# Sheet_1_2022-08-21.net
KiCad netlist of a schematic drawn in Altium Designer
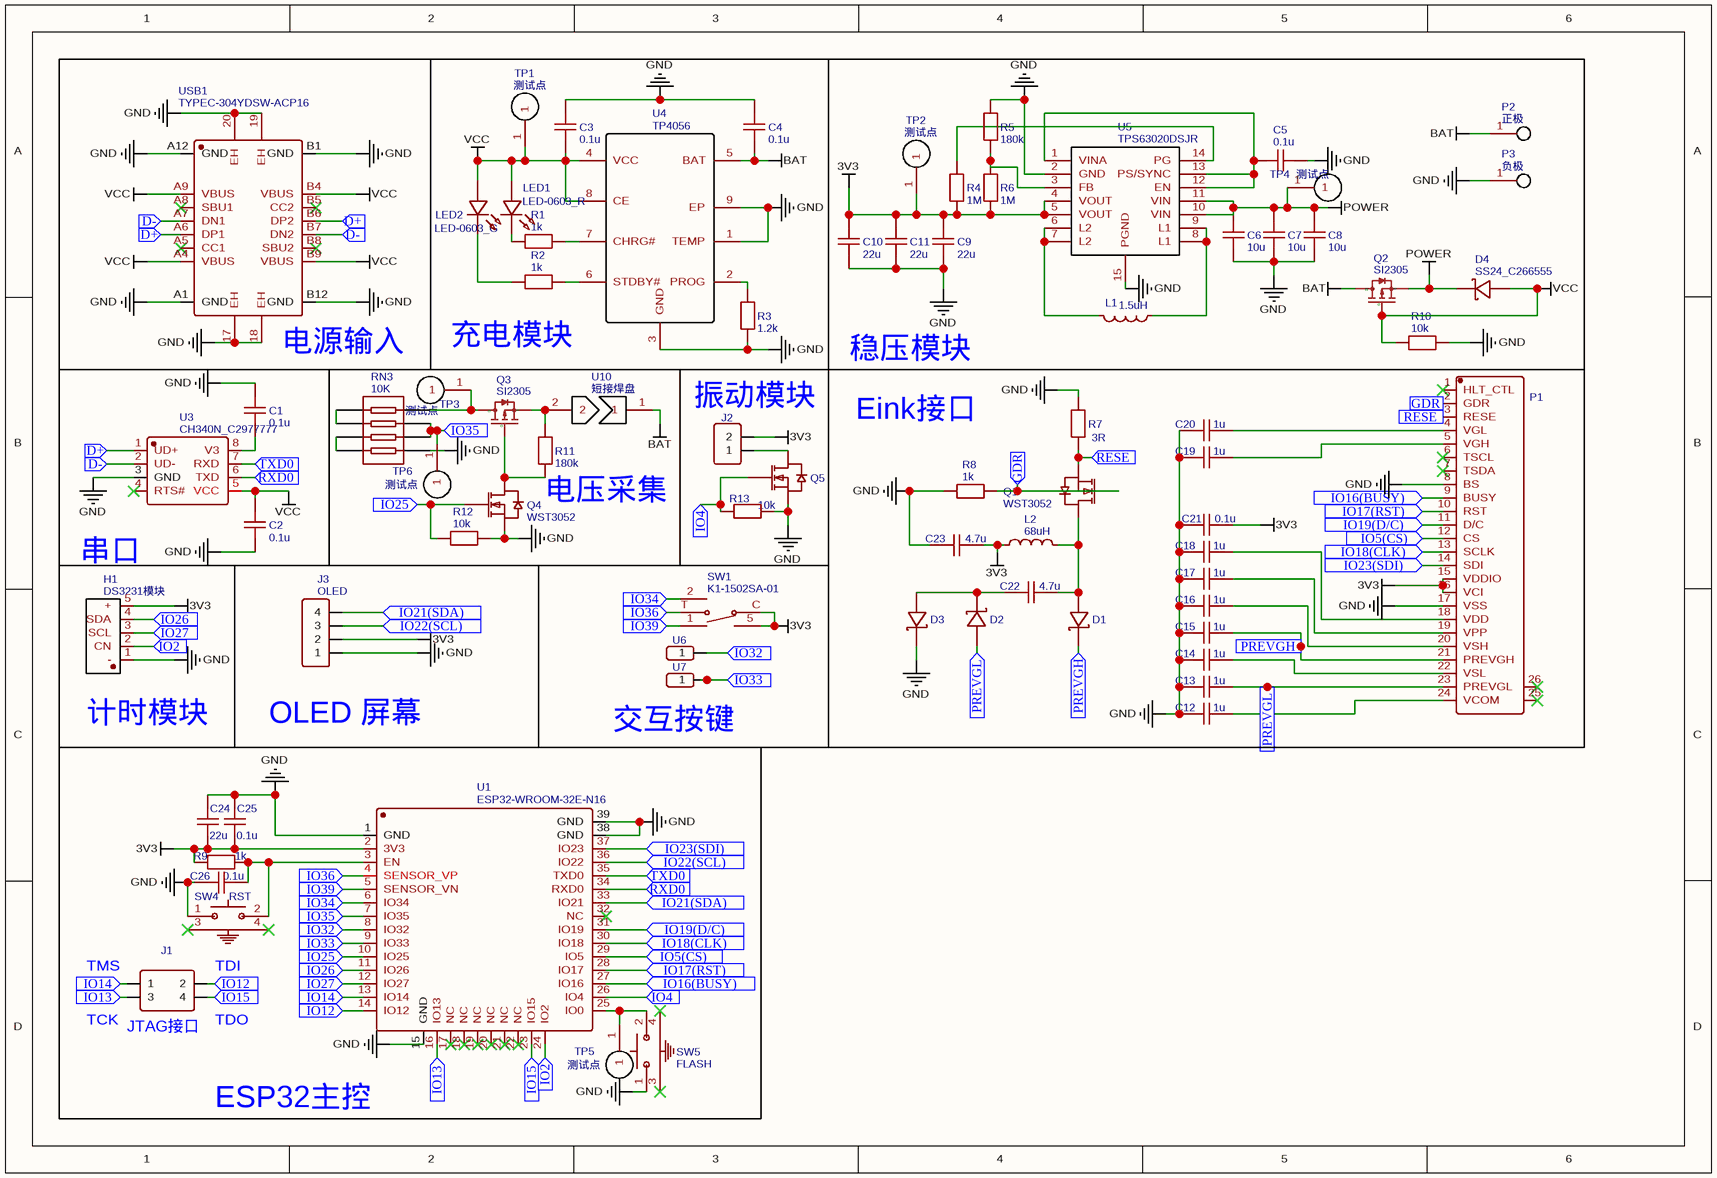
[diagram p0: Sheet_1_2022-08-21.schdoc]

(export (version "E")
  (design (tool "Eeschema 10.0.6"))
  (components
    (comp (ref "C1")
      (value "0.1u")
      (fields (field (name "CONTRIBUTOR") "LCEDA_Lib"))
      (libsource (lib "altium-import") (part "root_1_0.1u_"))
    )
    (comp (ref "C2")
      (value "0.1u")
      (fields (field (name "CONTRIBUTOR") "LCEDA_Lib"))
      (libsource (lib "altium-import") (part "root_1_0.1u_"))
    )
    (comp (ref "C3")
      (value "0.1u")
      (fields (field (name "CONTRIBUTOR") "LCEDA_Lib"))
      (libsource (lib "altium-import") (part "root_1_0.1u_"))
    )
    (comp (ref "C4")
      (value "0.1u")
      (fields (field (name "CONTRIBUTOR") "LCEDA_Lib"))
      (libsource (lib "altium-import") (part "root_1_0.1u_"))
    )
    (comp (ref "C5")
      (value "0.1u")
      (fields (field (name "CONTRIBUTOR") "LCEDA_Lib"))
      (libsource (lib "altium-import") (part "root_0_0.1u_"))
    )
    (comp (ref "C6")
      (value "10u")
      (fields (field (name "CONTRIBUTOR") "LCEDA_Lib"))
      (libsource (lib "altium-import") (part "root_1_10u_"))
    )
    (comp (ref "C7")
      (value "10u")
      (fields (field (name "CONTRIBUTOR") "LCEDA_Lib"))
      (libsource (lib "altium-import") (part "root_1_10u_"))
    )
    (comp (ref "C8")
      (value "10u")
      (fields (field (name "CONTRIBUTOR") "LCEDA_Lib"))
      (libsource (lib "altium-import") (part "root_1_10u_"))
    )
    (comp (ref "C9")
      (value "22u")
      (fields (field (name "CONTRIBUTOR") "LCEDA_Lib"))
      (libsource (lib "altium-import") (part "root_1_22u_"))
    )
    (comp (ref "C10")
      (value "22u")
      (fields (field (name "CONTRIBUTOR") "LCEDA_Lib"))
      (libsource (lib "altium-import") (part "root_1_22u_"))
    )
    (comp (ref "C11")
      (value "22u")
      (fields (field (name "CONTRIBUTOR") "LCEDA_Lib"))
      (libsource (lib "altium-import") (part "root_1_22u_"))
    )
    (comp (ref "C12")
      (value "1u")
      (fields (field (name "CONTRIBUTOR") "LCEDA_Lib"))
      (libsource (lib "altium-import") (part "root_0_1u_"))
    )
    (comp (ref "C13")
      (value "1u")
      (fields (field (name "CONTRIBUTOR") "LCEDA_Lib"))
      (libsource (lib "altium-import") (part "root_0_1u_"))
    )
    (comp (ref "C14")
      (value "1u")
      (fields (field (name "CONTRIBUTOR") "LCEDA_Lib"))
      (libsource (lib "altium-import") (part "root_2_1u_"))
    )
    (comp (ref "C15")
      (value "1u")
      (fields (field (name "CONTRIBUTOR") "LCEDA_Lib"))
      (libsource (lib "altium-import") (part "root_0_1u_"))
    )
    (comp (ref "C16")
      (value "1u")
      (fields (field (name "CONTRIBUTOR") "LCEDA_Lib"))
      (libsource (lib "altium-import") (part "root_0_1u_"))
    )
    (comp (ref "C17")
      (value "1u")
      (fields (field (name "CONTRIBUTOR") "LCEDA_Lib"))
      (libsource (lib "altium-import") (part "root_0_1u_"))
    )
    (comp (ref "C18")
      (value "1u")
      (fields (field (name "CONTRIBUTOR") "LCEDA_Lib"))
      (libsource (lib "altium-import") (part "root_0_1u_"))
    )
    (comp (ref "C19")
      (value "1u")
      (fields (field (name "CONTRIBUTOR") "LCEDA_Lib"))
      (libsource (lib "altium-import") (part "root_0_1u_"))
    )
    (comp (ref "C20")
      (value "1u")
      (fields (field (name "CONTRIBUTOR") "LCEDA_Lib"))
      (libsource (lib "altium-import") (part "root_0_1u_"))
    )
    (comp (ref "C21")
      (value "0.1u")
      (fields (field (name "CONTRIBUTOR") "LCEDA_Lib"))
      (libsource (lib "altium-import") (part "root_0_0.1u_"))
    )
    (comp (ref "C22")
      (value "4.7u")
      (fields (field (name "CONTRIBUTOR") "LCEDA_Lib"))
      (libsource (lib "altium-import") (part "root_0_4.7u_"))
    )
    (comp (ref "C23")
      (value "4.7u")
      (fields (field (name "CONTRIBUTOR") "LCEDA_Lib"))
      (libsource (lib "altium-import") (part "root_0_4.7u_"))
    )
    (comp (ref "C24")
      (value "22u")
      (fields (field (name "CONTRIBUTOR") "LCEDA_Lib"))
      (libsource (lib "altium-import") (part "root_1_22u_"))
    )
    (comp (ref "C25")
      (value "0.1u")
      (fields (field (name "CONTRIBUTOR") "LCEDA_Lib"))
      (libsource (lib "altium-import") (part "root_1_0.1u_"))
    )
    (comp (ref "C26")
      (value "0.1u")
      (fields (field (name "CONTRIBUTOR") "LCEDA_Lib"))
      (libsource (lib "altium-import") (part "root_2_0.1u_"))
    )
    (comp (ref "D1")
      (value "MBR0530_C232832")
      (fields
        (field (name "BOM_SUPPLIER PART") "C232832")
        (field (name "BOM_MANUFACTURER PART") "MBR0530")
        (field (name "CONTRIBUTOR") "LCSC")
      )
      (libsource (lib "altium-import") (part "root_1_MBR0530_C232832_"))
    )
    (comp (ref "D2")
      (value "MBR0530_C232832")
      (fields
        (field (name "BOM_SUPPLIER PART") "C232832")
        (field (name "BOM_MANUFACTURER PART") "MBR0530")
        (field (name "CONTRIBUTOR") "LCSC")
      )
      (libsource (lib "altium-import") (part "root_3_MBR0530_C232832_"))
    )
    (comp (ref "D3")
      (value "MBR0530_C232832")
      (fields
        (field (name "BOM_SUPPLIER PART") "C232832")
        (field (name "BOM_MANUFACTURER PART") "MBR0530")
        (field (name "CONTRIBUTOR") "LCSC")
      )
      (libsource (lib "altium-import") (part "root_1_MBR0530_C232832_"))
    )
    (comp (ref "D4")
      (value "SS24_C266555")
      (fields
        (field (name "BOM_SUPPLIER PART") "C266555")
        (field (name "BOM_MANUFACTURER PART") "SS24")
        (field (name "CONTRIBUTOR") "LCSC")
      )
      (libsource (lib "altium-import") (part "root_0_SS24_C266555_"))
    )
    (comp (ref "H1")
      (value "DS3231模块")
      (fields
        (field (name "BOM_SUPPLIER PART") "C492404")
        (field (name "BOM_MANUFACTURER PART") "PZ254V-11-05P")
        (field (name "CONTRIBUTOR") "LCSC")
      )
      (libsource (lib "altium-import") (part "root_2_DS3231模块_"))
    )
    (comp (ref "J1")
      (value "HDR-M-2.54_2x2")
      (fields (field (name "BOM_SUPPLIER PART") "C66690") (field (name "CONTRIBUTOR") "LCEDA_Lib"))
      (libsource (lib "altium-import") (part "root_0_HDR-M-2.54_2x2_"))
    )
    (comp (ref "J2")
      (value "HDR-M-2.54_1x2")
      (fields (field (name "BOM_SUPPLIER PART") "C124375") (field (name "CONTRIBUTOR") "LCEDA_Lib"))
      (libsource (lib "altium-import") (part "root_2_HDR-M-2.54_1x2_"))
    )
    (comp (ref "J3")
      (value "OLED")
      (fields (field (name "BOM_SUPPLIER PART") "C124378") (field (name "CONTRIBUTOR") "LCEDA_Lib"))
      (libsource (lib "altium-import") (part "root_2_OLED_"))
    )
    (comp (ref "L1")
      (value "1.5uH")
      (fields
        (field (name "BOM_SUPPLIER PART") "C340206")
        (field (name "BOM_MANUFACTURER PART") "ASWPA4035S1R5MT")
        (field (name "CONTRIBUTOR") "LCSC")
      )
      (libsource (lib "altium-import") (part "root_2_1.5uH_"))
    )
    (comp (ref "L2")
      (value "68uH")
      (fields
        (field (name "BOM_SUPPLIER PART") "C340229")
        (field (name "BOM_MANUFACTURER PART") "ASWPA6055S680MT")
        (field (name "CONTRIBUTOR") "LCSC")
      )
      (libsource (lib "altium-import") (part "root_0_68uH_"))
    )
    (comp (ref "LED1")
      (value "LED-0603_R")
      (fields
        (field (name "BOM_MANUFACTURER PART") "19-217/R6C-AL1M2VY/3T")
        (field (name "BOM_SUPPLIER PART") "C72044")
        (field (name "CONTRIBUTOR") "LCEDA_01")
      )
      (libsource (lib "altium-import") (part "root_3_LED-0603_R_"))
    )
    (comp (ref "LED2")
      (value "LED-0603_G")
      (fields
        (field (name "BOM_MANUFACTURER PART") "19-217/GHC-YR1S2/3T")
        (field (name "BOM_SUPPLIER PART") "C72043")
        (field (name "CONTRIBUTOR") "LCEDA_Lib")
      )
      (libsource (lib "altium-import") (part "root_3_LED-0603_G_"))
    )
    (comp (ref "P1")
      (value "微雪电子 24pin 电子墨水屏幕底座  /FPC 0.5MM 24P")
      (fields
        (field (name "BOM_MANUFACTURER PART") "FPC 0.5MM 24P Pull type H2.0mm Under the next")
        (field (name "BOM_SUPPLIER PART") "C11057")
        (field (name "CONTRIBUTOR") "jszszzy")
      )
      (libsource (lib "altium-import") (part "root_0_微雪电子 24pin 电子墨水屏幕底座  /FPC 0.5MM 24P_"))
    )
    (comp (ref "P2")
      (value "正极")
      (fields (field (name "CONTRIBUTOR") "Newguy"))
      (libsource (lib "altium-import") (part "root_2_正极_"))
    )
    (comp (ref "P3")
      (value "负极")
      (fields (field (name "CONTRIBUTOR") "Newguy"))
      (libsource (lib "altium-import") (part "root_2_负极_"))
    )
    (comp (ref "Q1")
      (value "WST3052")
      (fields (field (name "BOM_SUPPLIER PART") "C719079") (field (name "CONTRIBUTOR") "LCSC"))
      (libsource (lib "altium-import") (part "root_2_WST3052_"))
    )
    (comp (ref "Q2")
      (value "SI2305")
      (fields (field (name "BOM_SUPPLIER PART") "C181088") (field (name "CONTRIBUTOR") "LCSC"))
      (libsource (lib "altium-import") (part "root_1_SI2305_"))
    )
    (comp (ref "Q3")
      (value "SI2305")
      (fields (field (name "BOM_SUPPLIER PART") "C181088") (field (name "CONTRIBUTOR") "LCSC"))
      (libsource (lib "altium-import") (part "root_1_SI2305_"))
    )
    (comp (ref "Q4")
      (value "WST3052")
      (fields (field (name "BOM_SUPPLIER PART") "C719079") (field (name "CONTRIBUTOR") "LCSC"))
      (libsource (lib "altium-import") (part "root_0_WST3052_"))
    )
    (comp (ref "Q5")
      (value "WST3052")
      (fields (field (name "BOM_SUPPLIER PART") "C719079") (field (name "CONTRIBUTOR") "LCSC"))
      (libsource (lib "altium-import") (part "root_0_WST3052_"))
    )
    (comp (ref "R1")
      (value "1k")
      (fields (field (name "CONTRIBUTOR") "LCEDA_Lib"))
      (libsource (lib "altium-import") (part "root_0_1k_"))
    )
    (comp (ref "R2")
      (value "1k")
      (fields (field (name "CONTRIBUTOR") "LCEDA_Lib"))
      (libsource (lib "altium-import") (part "root_0_1k_"))
    )
    (comp (ref "R3")
      (value "1.2k")
      (fields (field (name "CONTRIBUTOR") "LCEDA_Lib"))
      (libsource (lib "altium-import") (part "root_1_1.2k_"))
    )
    (comp (ref "R4")
      (value "1M")
      (fields (field (name "CONTRIBUTOR") "LCEDA_Lib"))
      (libsource (lib "altium-import") (part "root_1_1M_"))
    )
    (comp (ref "R5")
      (value "180k")
      (fields (field (name "CONTRIBUTOR") "LCEDA_Lib"))
      (libsource (lib "altium-import") (part "root_1_180k_"))
    )
    (comp (ref "R6")
      (value "1M")
      (fields (field (name "CONTRIBUTOR") "LCEDA_Lib"))
      (libsource (lib "altium-import") (part "root_1_1M_"))
    )
    (comp (ref "R7")
      (value "3R")
      (fields (field (name "CONTRIBUTOR") "LCEDA_Lib"))
      (libsource (lib "altium-import") (part "root_1_3R_"))
    )
    (comp (ref "R8")
      (value "1k")
      (fields (field (name "CONTRIBUTOR") "LCEDA_Lib"))
      (libsource (lib "altium-import") (part "root_2_1k_"))
    )
    (comp (ref "R9")
      (value "1k")
      (fields (field (name "CONTRIBUTOR") "LCEDA_Lib"))
      (libsource (lib "altium-import") (part "root_0_1k_"))
    )
    (comp (ref "R10")
      (value "10k")
      (fields (field (name "CONTRIBUTOR") "LCEDA_Lib"))
      (libsource (lib "altium-import") (part "root_2_10k_"))
    )
    (comp (ref "R11")
      (value "180k")
      (fields (field (name "CONTRIBUTOR") "LCEDA_Lib"))
      (libsource (lib "altium-import") (part "root_1_180k_"))
    )
    (comp (ref "R12")
      (value "10k")
      (fields (field (name "CONTRIBUTOR") "LCEDA_Lib"))
      (libsource (lib "altium-import") (part "root_0_10k_"))
    )
    (comp (ref "R13")
      (value "10k")
      (fields (field (name "CONTRIBUTOR") "LCEDA_Lib"))
      (libsource (lib "altium-import") (part "root_0_10k_"))
    )
    (comp (ref "RN3")
      (value "10K")
      (fields
        (field (name "BOM_MANUFACTURER PART") "YC164-JR-0710KL")
        (field (name "BOM_SUPPLIER PART") "C107374")
      )
      (libsource (lib "altium-import") (part "root_3_10K_"))
    )
    (comp (ref "SW1")
      (value "K1-1502SA-01")
      (fields (field (name "BOM_SUPPLIER PART") "C145915") (field (name "CONTRIBUTOR") "LCSC"))
      (libsource (lib "altium-import") (part "root_2_K1-1502SA-01_"))
    )
    (comp (ref "SW4")
      (value "RST")
      (fields
        (field (name "BOM_SUPPLIER PART") "C255804")
        (field (name "BOM_MANUFACTURER PART") "1TS002G-2500-3500")
        (field (name "CONTRIBUTOR") "LCSC")
      )
      (libsource (lib "altium-import") (part "root_0_RST_"))
    )
    (comp (ref "SW5")
      (value "FLASH")
      (fields
        (field (name "BOM_SUPPLIER PART") "C255804")
        (field (name "BOM_MANUFACTURER PART") "1TS002G-2500-3500")
        (field (name "CONTRIBUTOR") "LCSC")
      )
      (libsource (lib "altium-import") (part "root_1_FLASH_"))
    )
    (comp (ref "TP1")
      (value "测试点")
      (fields (field (name "CONTRIBUTOR") "CSSC"))
      (libsource (lib "altium-import") (part "root_3_测试点_"))
    )
    (comp (ref "TP2")
      (value "测试点")
      (fields (field (name "CONTRIBUTOR") "CSSC"))
      (libsource (lib "altium-import") (part "root_3_测试点_"))
    )
    (comp (ref "TP3")
      (value "测试点")
      (fields (field (name "CONTRIBUTOR") "CSSC"))
      (libsource (lib "altium-import") (part "root_0_测试点_"))
    )
    (comp (ref "TP4")
      (value "测试点")
      (fields (field (name "CONTRIBUTOR") "CSSC"))
      (libsource (lib "altium-import") (part "root_2_测试点_"))
    )
    (comp (ref "TP5")
      (value "测试点")
      (fields (field (name "CONTRIBUTOR") "CSSC"))
      (libsource (lib "altium-import") (part "root_1_测试点_"))
    )
    (comp (ref "TP6")
      (value "测试点")
      (fields (field (name "CONTRIBUTOR") "CSSC"))
      (libsource (lib "altium-import") (part "root_1_测试点_"))
    )
    (comp (ref "U1")
      (value "ESP32-WROOM-32E-N16")
      (fields (field (name "BOM_SUPPLIER PART") "C2973650") (field (name "CONTRIBUTOR") "lcsc"))
      (libsource (lib "altium-import") (part "root_0_ESP32-WROOM-32E-N16_"))
    )
    (comp (ref "U3")
      (value "CH340N_C2977777")
      (fields
        (field (name "BOM_SUPPLIER PART") "C2977777")
        (field (name "BOM_MANUFACTURER PART") "CH340N")
        (field (name "CONTRIBUTOR") "LCSC")
      )
      (libsource (lib "altium-import") (part "root_0_CH340N_C2977777_"))
    )
    (comp (ref "U4")
      (value "TP4056")
      (fields (field (name "BOM_SUPPLIER PART") "C16581") (field (name "CONTRIBUTOR") "Guest"))
      (libsource (lib "altium-import") (part "root_0_TP4056_"))
    )
    (comp (ref "U5")
      (value "TPS63020DSJR")
      (fields (field (name "BOM_SUPPLIER PART") "C15483"))
      (libsource (lib "altium-import") (part "root_0_TPS63020DSJR_"))
    )
    (comp (ref "U6")
      (value "触摸焊盘")
      (fields (field (name "CONTRIBUTOR") "goodwood"))
      (libsource (lib "altium-import") (part "root_0_触摸焊盘_"))
    )
    (comp (ref "U7")
      (value "触摸焊盘")
      (fields (field (name "CONTRIBUTOR") "goodwood"))
      (libsource (lib "altium-import") (part "root_0_触摸焊盘_"))
    )
    (comp (ref "U10")
      (value "短接焊盘")
      (fields (field (name "CONTRIBUTOR") "laimoren"))
      (libsource (lib "altium-import") (part "root_2_短接焊盘_"))
    )
    (comp (ref "USB1")
      (value "TYPEC-304YDSW-ACP16")
      (fields (field (name "BOM_SUPPLIER PART") "C2840391") (field (name "CONTRIBUTOR") "LCSC"))
      (libsource (lib "altium-import") (part "root_0_TYPEC-304YDSW-ACP16_"))
    )
  )
  (nets
    (net (code "1") (name "/D+") (class "Default")
      (node (ref "U3") (pin "1") (pinfunction "UD+_1") (pintype "passive"))
      (node (ref "USB1") (pin "A6") (pinfunction "DP1_A6") (pintype "passive"))
      (node (ref "USB1") (pin "B6") (pinfunction "DP2_B6") (pintype "passive"))
    )
    (net (code "2") (name "/D-") (class "Default")
      (node (ref "U3") (pin "2") (pinfunction "UD-_2") (pintype "passive"))
      (node (ref "USB1") (pin "A7") (pinfunction "DN1_A7") (pintype "passive"))
      (node (ref "USB1") (pin "B7") (pinfunction "DN2_B7") (pintype "passive"))
    )
    (net (code "3") (name "/GDR") (class "Default")
      (node (ref "P1") (pin "2") (pinfunction "GDR_2") (pintype "passive"))
      (node (ref "Q1") (pin "1") (pinfunction "G_1") (pintype "passive"))
      (node (ref "R8") (pin "1") (pinfunction "1_1") (pintype "passive"))
    )
    (net (code "4") (name "/IO2") (class "Default")
      (node (ref "H1") (pin "2") (pinfunction "CN_2") (pintype "passive"))
      (node (ref "U1") (pin "24") (pinfunction "IO2_24") (pintype "passive"))
    )
    (net (code "5") (name "/IO4") (class "Default")
      (node (ref "Q5") (pin "1") (pinfunction "G_1") (pintype "passive"))
      (node (ref "R13") (pin "1") (pinfunction "1_1") (pintype "passive"))
      (node (ref "U1") (pin "26") (pinfunction "IO4_26") (pintype "passive"))
    )
    (net (code "6") (name "/IO5(CS)") (class "Default")
      (node (ref "P1") (pin "12") (pinfunction "CS_12") (pintype "passive"))
      (node (ref "U1") (pin "29") (pinfunction "IO5_29") (pintype "passive"))
    )
    (net (code "7") (name "/IO12") (class "Default")
      (node (ref "J1") (pin "2") (pinfunction "2_2") (pintype "passive"))
      (node (ref "U1") (pin "14") (pinfunction "IO12_14") (pintype "passive"))
    )
    (net (code "8") (name "/IO13") (class "Default")
      (node (ref "J1") (pin "3") (pinfunction "3_3") (pintype "passive"))
      (node (ref "U1") (pin "16") (pinfunction "IO13_16") (pintype "passive"))
    )
    (net (code "9") (name "/IO14") (class "Default")
      (node (ref "J1") (pin "1") (pinfunction "1_1") (pintype "passive"))
      (node (ref "U1") (pin "13") (pinfunction "IO14_13") (pintype "passive"))
    )
    (net (code "10") (name "/IO15") (class "Default")
      (node (ref "J1") (pin "4") (pinfunction "4_4") (pintype "passive"))
      (node (ref "U1") (pin "23") (pinfunction "IO15_23") (pintype "passive"))
    )
    (net (code "11") (name "/IO16(BUSY)") (class "Default")
      (node (ref "P1") (pin "9") (pinfunction "BUSY_9") (pintype "passive"))
      (node (ref "U1") (pin "27") (pinfunction "IO16_27") (pintype "passive"))
    )
    (net (code "12") (name "/IO17(RST)") (class "Default")
      (node (ref "P1") (pin "10") (pinfunction "RST_10") (pintype "passive"))
      (node (ref "U1") (pin "28") (pinfunction "IO17_28") (pintype "passive"))
    )
    (net (code "13") (name "/IO18(CLK)") (class "Default")
      (node (ref "P1") (pin "13") (pinfunction "SCLK_13") (pintype "passive"))
      (node (ref "U1") (pin "30") (pinfunction "IO18_30") (pintype "passive"))
    )
    (net (code "14") (name "/IO19(D{slash}C)") (class "Default")
      (node (ref "P1") (pin "11") (pinfunction "D/C_11") (pintype "passive"))
      (node (ref "U1") (pin "31") (pinfunction "IO19_31") (pintype "passive"))
    )
    (net (code "15") (name "/IO21(SDA)") (class "Default")
      (node (ref "J3") (pin "4") (pinfunction "4_4") (pintype "passive"))
      (node (ref "U1") (pin "33") (pinfunction "IO21_33") (pintype "passive"))
    )
    (net (code "16") (name "/IO22(SCL)") (class "Default")
      (node (ref "J3") (pin "3") (pinfunction "3_3") (pintype "passive"))
      (node (ref "U1") (pin "36") (pinfunction "IO22_36") (pintype "passive"))
    )
    (net (code "17") (name "/IO23(SDI)") (class "Default")
      (node (ref "P1") (pin "14") (pinfunction "SDI_14") (pintype "passive"))
      (node (ref "U1") (pin "37") (pinfunction "IO23_37") (pintype "passive"))
    )
    (net (code "18") (name "/IO25") (class "Default")
      (node (ref "Q4") (pin "1") (pinfunction "G_1") (pintype "passive"))
      (node (ref "R12") (pin "1") (pinfunction "1_1") (pintype "passive"))
      (node (ref "U1") (pin "10") (pinfunction "IO25_10") (pintype "passive"))
    )
    (net (code "19") (name "/IO26") (class "Default")
      (node (ref "H1") (pin "4") (pinfunction "SDA_4") (pintype "passive"))
      (node (ref "U1") (pin "11") (pinfunction "IO26_11") (pintype "passive"))
    )
    (net (code "20") (name "/IO27") (class "Default")
      (node (ref "H1") (pin "3") (pinfunction "SCL_3") (pintype "passive"))
      (node (ref "U1") (pin "12") (pinfunction "IO27_12") (pintype "passive"))
    )
    (net (code "21") (name "/IO32") (class "Default")
      (node (ref "U1") (pin "8") (pinfunction "IO32_8") (pintype "passive"))
      (node (ref "U6") (pin "1") (pinfunction "1_1") (pintype "passive"))
    )
    (net (code "22") (name "/IO33") (class "Default")
      (node (ref "U1") (pin "9") (pinfunction "IO33_9") (pintype "passive"))
      (node (ref "U7") (pin "1") (pinfunction "1_1") (pintype "passive"))
    )
    (net (code "23") (name "/IO34") (class "Default")
      (node (ref "SW1") (pin "2") (pinfunction "2_2") (pintype "passive"))
      (node (ref "U1") (pin "6") (pinfunction "IO34_6") (pintype "passive"))
    )
    (net (code "24") (name "/IO35") (class "Default")
      (node (ref "RN3") (pin "6") (pinfunction "6_6") (pintype "passive"))
      (node (ref "RN3") (pin "7") (pinfunction "7_7") (pintype "passive"))
      (node (ref "TP6") (pin "1") (pinfunction "1_1") (pintype "passive"))
      (node (ref "U1") (pin "7") (pinfunction "IO35_7") (pintype "passive"))
    )
    (net (code "25") (name "/IO36") (class "Default")
      (node (ref "SW1") (pin "T") (pinfunction "T_T") (pintype "passive"))
      (node (ref "U1") (pin "4") (pinfunction "SENSOR_VP_4") (pintype "passive"))
    )
    (net (code "26") (name "/IO39") (class "Default")
      (node (ref "SW1") (pin "1") (pinfunction "1_1") (pintype "passive"))
      (node (ref "U1") (pin "5") (pinfunction "SENSOR_VN_5") (pintype "passive"))
    )
    (net (code "27") (name "/PREVGH") (class "Default")
      (node (ref "C15") (pin "2") (pinfunction "2_2") (pintype "passive"))
      (node (ref "D1") (pin "1") (pinfunction "K_1") (pintype "passive"))
      (node (ref "P1") (pin "21") (pinfunction "PREVGH_21") (pintype "passive"))
    )
    (net (code "28") (name "/PREVGL") (class "Default")
      (node (ref "C13") (pin "2") (pinfunction "2_2") (pintype "passive"))
      (node (ref "D2") (pin "2") (pinfunction "A_2") (pintype "passive"))
      (node (ref "P1") (pin "23") (pinfunction "PREVGL_23") (pintype "passive"))
    )
    (net (code "29") (name "/RESE") (class "Default")
      (node (ref "P1") (pin "3") (pinfunction "RESE_3") (pintype "passive"))
      (node (ref "Q1") (pin "2") (pinfunction "S_2") (pintype "passive"))
      (node (ref "R7") (pin "1") (pinfunction "1_1") (pintype "passive"))
    )
    (net (code "30") (name "/RXD0") (class "Default")
      (node (ref "U1") (pin "34") (pinfunction "RXD0_34") (pintype "passive"))
      (node (ref "U3") (pin "6") (pinfunction "TXD_6") (pintype "passive"))
    )
    (net (code "31") (name "/TXD0") (class "Default")
      (node (ref "U1") (pin "35") (pinfunction "TXD0_35") (pintype "passive"))
      (node (ref "U3") (pin "7") (pinfunction "RXD_7") (pintype "passive"))
    )
    (net (code "32") (name "3V3") (class "Default")
      (node (ref "C10") (pin "2") (pinfunction "2_2") (pintype "passive"))
      (node (ref "C11") (pin "2") (pinfunction "2_2") (pintype "passive"))
      (node (ref "C21") (pin "2") (pinfunction "2_2") (pintype "passive"))
      (node (ref "C23") (pin "2") (pinfunction "2_2") (pintype "passive"))
      (node (ref "C24") (pin "1") (pinfunction "1_1") (pintype "passive"))
      (node (ref "C25") (pin "1") (pinfunction "1_1") (pintype "passive"))
      (node (ref "C9") (pin "2") (pinfunction "2_2") (pintype "passive"))
      (node (ref "H1") (pin "5") (pinfunction "+_5") (pintype "passive"))
      (node (ref "J2") (pin "2") (pinfunction "2_2") (pintype "passive"))
      (node (ref "J3") (pin "2") (pinfunction "2_2") (pintype "passive"))
      (node (ref "L2") (pin "1") (pinfunction "1_1") (pintype "passive"))
      (node (ref "P1") (pin "15") (pinfunction "VDDIO_15") (pintype "passive"))
      (node (ref "P1") (pin "16") (pinfunction "VCI_16") (pintype "passive"))
      (node (ref "R4") (pin "1") (pinfunction "1_1") (pintype "passive"))
      (node (ref "R6") (pin "1") (pinfunction "1_1") (pintype "passive"))
      (node (ref "R9") (pin "1") (pinfunction "1_1") (pintype "passive"))
      (node (ref "SW1") (pin "5") (pinfunction "5_5") (pintype "passive"))
      (node (ref "SW1") (pin "C") (pinfunction "C_C") (pintype "passive"))
      (node (ref "TP2") (pin "1") (pinfunction "1_1") (pintype "passive"))
      (node (ref "U1") (pin "2") (pinfunction "3V3_2") (pintype "passive"))
      (node (ref "U5") (pin "4") (pinfunction "VOUT_4") (pintype "passive"))
      (node (ref "U5") (pin "5") (pinfunction "VOUT_5") (pintype "passive"))
    )
    (net (code "33") (name "BAT") (class "Default")
      (node (ref "C4") (pin "1") (pinfunction "1_1") (pintype "passive"))
      (node (ref "P2") (pin "1") (pinfunction "1_1") (pintype "passive"))
      (node (ref "Q2") (pin "3") (pinfunction "D_3") (pintype "passive"))
      (node (ref "U10") (pin "1") (pinfunction "1_1") (pintype "passive"))
      (node (ref "U4") (pin "5") (pinfunction "BAT_5") (pintype "passive"))
    )
    (net (code "34") (name "GND") (class "Default")
      (node (ref "C1") (pin "2") (pinfunction "2_2") (pintype "passive"))
      (node (ref "C10") (pin "1") (pinfunction "1_1") (pintype "passive"))
      (node (ref "C11") (pin "1") (pinfunction "1_1") (pintype "passive"))
      (node (ref "C12") (pin "1") (pinfunction "1_1") (pintype "passive"))
      (node (ref "C13") (pin "1") (pinfunction "1_1") (pintype "passive"))
      (node (ref "C14") (pin "2") (pinfunction "2_2") (pintype "passive"))
      (node (ref "C15") (pin "1") (pinfunction "1_1") (pintype "passive"))
      (node (ref "C16") (pin "1") (pinfunction "1_1") (pintype "passive"))
      (node (ref "C17") (pin "1") (pinfunction "1_1") (pintype "passive"))
      (node (ref "C18") (pin "1") (pinfunction "1_1") (pintype "passive"))
      (node (ref "C19") (pin "1") (pinfunction "1_1") (pintype "passive"))
      (node (ref "C2") (pin "1") (pinfunction "1_1") (pintype "passive"))
      (node (ref "C20") (pin "1") (pinfunction "1_1") (pintype "passive"))
      (node (ref "C21") (pin "1") (pinfunction "1_1") (pintype "passive"))
      (node (ref "C23") (pin "1") (pinfunction "1_1") (pintype "passive"))
      (node (ref "C24") (pin "2") (pinfunction "2_2") (pintype "passive"))
      (node (ref "C25") (pin "2") (pinfunction "2_2") (pintype "passive"))
      (node (ref "C26") (pin "2") (pinfunction "2_2") (pintype "passive"))
      (node (ref "C3") (pin "2") (pinfunction "2_2") (pintype "passive"))
      (node (ref "C4") (pin "2") (pinfunction "2_2") (pintype "passive"))
      (node (ref "C5") (pin "2") (pinfunction "2_2") (pintype "passive"))
      (node (ref "C6") (pin "1") (pinfunction "1_1") (pintype "passive"))
      (node (ref "C7") (pin "1") (pinfunction "1_1") (pintype "passive"))
      (node (ref "C8") (pin "1") (pinfunction "1_1") (pintype "passive"))
      (node (ref "C9") (pin "1") (pinfunction "1_1") (pintype "passive"))
      (node (ref "D3") (pin "1") (pinfunction "K_1") (pintype "passive"))
      (node (ref "H1") (pin "1") (pinfunction "-_1") (pintype "passive"))
      (node (ref "J3") (pin "1") (pinfunction "1_1") (pintype "passive"))
      (node (ref "P1") (pin "17") (pinfunction "VSS_17") (pintype "passive"))
      (node (ref "P1") (pin "8") (pinfunction "BS_8") (pintype "passive"))
      (node (ref "P3") (pin "1") (pinfunction "1_1") (pintype "passive"))
      (node (ref "Q4") (pin "2") (pinfunction "S_2") (pintype "passive"))
      (node (ref "Q5") (pin "2") (pinfunction "S_2") (pintype "passive"))
      (node (ref "R10") (pin "1") (pinfunction "1_1") (pintype "passive"))
      (node (ref "R12") (pin "2") (pinfunction "2_2") (pintype "passive"))
      (node (ref "R13") (pin "2") (pinfunction "2_2") (pintype "passive"))
      (node (ref "R3") (pin "1") (pinfunction "1_1") (pintype "passive"))
      (node (ref "R5") (pin "2") (pinfunction "2_2") (pintype "passive"))
      (node (ref "R7") (pin "2") (pinfunction "2_2") (pintype "passive"))
      (node (ref "R8") (pin "2") (pinfunction "2_2") (pintype "passive"))
      (node (ref "RN3") (pin "5") (pinfunction "5_5") (pintype "passive"))
      (node (ref "SW4") (pin "1") (pinfunction "1_1") (pintype "passive"))
      (node (ref "SW5") (pin "1") (pinfunction "1_1") (pintype "passive"))
      (node (ref "U1") (pin "1") (pinfunction "GND_1") (pintype "passive"))
      (node (ref "U1") (pin "15") (pinfunction "GND_15") (pintype "passive"))
      (node (ref "U1") (pin "38") (pinfunction "GND_38") (pintype "passive"))
      (node (ref "U1") (pin "39") (pinfunction "GND_39") (pintype "passive"))
      (node (ref "U3") (pin "3") (pinfunction "GND_3") (pintype "passive"))
      (node (ref "U4") (pin "1") (pinfunction "TEMP_1") (pintype "passive"))
      (node (ref "U4") (pin "3") (pinfunction "GND_3") (pintype "passive"))
      (node (ref "U4") (pin "9") (pinfunction "EP_9") (pintype "passive"))
      (node (ref "U5") (pin "15") (pinfunction "PGND_15") (pintype "passive"))
      (node (ref "U5") (pin "2") (pinfunction "GND_2") (pintype "passive"))
      (node (ref "USB1") (pin "17") (pinfunction "EH_17") (pintype "passive"))
      (node (ref "USB1") (pin "18") (pinfunction "EH_18") (pintype "passive"))
      (node (ref "USB1") (pin "19") (pinfunction "EH_19") (pintype "passive"))
      (node (ref "USB1") (pin "20") (pinfunction "EH_20") (pintype "passive"))
      (node (ref "USB1") (pin "A1") (pinfunction "GND_A1") (pintype "passive"))
      (node (ref "USB1") (pin "A12") (pinfunction "GND_A12") (pintype "passive"))
      (node (ref "USB1") (pin "B1") (pinfunction "GND_B1") (pintype "passive"))
      (node (ref "USB1") (pin "B12") (pinfunction "GND_B12") (pintype "passive"))
    )
    (net (code "35") (name "Net-(D1-A)") (class "Default")
      (node (ref "C22") (pin "2") (pinfunction "2_2") (pintype "passive"))
      (node (ref "D1") (pin "2") (pinfunction "A_2") (pintype "passive"))
      (node (ref "L2") (pin "2") (pinfunction "2_2") (pintype "passive"))
      (node (ref "Q1") (pin "3") (pinfunction "D_3") (pintype "passive"))
    )
    (net (code "36") (name "Net-(D2-K)") (class "Default")
      (node (ref "C22") (pin "1") (pinfunction "1_1") (pintype "passive"))
      (node (ref "D2") (pin "1") (pinfunction "K_1") (pintype "passive"))
      (node (ref "D3") (pin "2") (pinfunction "A_2") (pintype "passive"))
    )
    (net (code "37") (name "Net-(L1-Pad1)") (class "Default")
      (node (ref "L1") (pin "1") (pinfunction "1_1") (pintype "passive"))
      (node (ref "U5") (pin "8") (pinfunction "L1_8") (pintype "passive"))
      (node (ref "U5") (pin "9") (pinfunction "L1_9") (pintype "passive"))
    )
    (net (code "38") (name "Net-(L1-Pad2)") (class "Default")
      (node (ref "L1") (pin "2") (pinfunction "2_2") (pintype "passive"))
      (node (ref "U5") (pin "6") (pinfunction "L2_6") (pintype "passive"))
      (node (ref "U5") (pin "7") (pinfunction "L2_7") (pintype "passive"))
    )
    (net (code "39") (name "Net-(LED1-Pad2)") (class "Default")
      (node (ref "LED1") (pin "2") (pinfunction "2_2") (pintype "passive"))
      (node (ref "R1") (pin "1") (pinfunction "1_1") (pintype "passive"))
    )
    (net (code "40") (name "Net-(LED2-Pad2)") (class "Default")
      (node (ref "LED2") (pin "2") (pinfunction "2_2") (pintype "passive"))
      (node (ref "R2") (pin "1") (pinfunction "1_1") (pintype "passive"))
    )
    (net (code "41") (name "Net-(P1-VCOM)") (class "Default")
      (node (ref "C12") (pin "2") (pinfunction "2_2") (pintype "passive"))
      (node (ref "P1") (pin "24") (pinfunction "VCOM_24") (pintype "passive"))
    )
    (net (code "42") (name "Net-(P1-VDD)") (class "Default")
      (node (ref "C18") (pin "2") (pinfunction "2_2") (pintype "passive"))
      (node (ref "P1") (pin "18") (pinfunction "VDD_18") (pintype "passive"))
    )
    (net (code "43") (name "Net-(P1-VGH)") (class "Default")
      (node (ref "C19") (pin "2") (pinfunction "2_2") (pintype "passive"))
      (node (ref "P1") (pin "5") (pinfunction "VGH_5") (pintype "passive"))
    )
    (net (code "44") (name "Net-(P1-VGL)") (class "Default")
      (node (ref "C20") (pin "2") (pinfunction "2_2") (pintype "passive"))
      (node (ref "P1") (pin "4") (pinfunction "VGL_4") (pintype "passive"))
    )
    (net (code "45") (name "Net-(P1-VPP)") (class "Default")
      (node (ref "C17") (pin "2") (pinfunction "2_2") (pintype "passive"))
      (node (ref "P1") (pin "19") (pinfunction "VPP_19") (pintype "passive"))
    )
    (net (code "46") (name "Net-(P1-VSH)") (class "Default")
      (node (ref "C16") (pin "2") (pinfunction "2_2") (pintype "passive"))
      (node (ref "P1") (pin "20") (pinfunction "VSH_20") (pintype "passive"))
    )
    (net (code "47") (name "Net-(P1-VSL)") (class "Default")
      (node (ref "C14") (pin "1") (pinfunction "1_1") (pintype "passive"))
      (node (ref "P1") (pin "22") (pinfunction "VSL_22") (pintype "passive"))
    )
    (net (code "48") (name "Net-(Q3-D)") (class "Default")
      (node (ref "Q3") (pin "3") (pinfunction "D_3") (pintype "passive"))
      (node (ref "RN3") (pin "8") (pinfunction "8_8") (pintype "passive"))
      (node (ref "TP3") (pin "1") (pinfunction "1_1") (pintype "passive"))
    )
    (net (code "49") (name "Net-(Q3-G)") (class "Default")
      (node (ref "Q3") (pin "1") (pinfunction "G_1") (pintype "passive"))
      (node (ref "Q4") (pin "3") (pinfunction "D_3") (pintype "passive"))
      (node (ref "R11") (pin "1") (pinfunction "1_1") (pintype "passive"))
    )
    (net (code "50") (name "Net-(Q3-S)") (class "Default")
      (node (ref "Q3") (pin "2") (pinfunction "S_2") (pintype "passive"))
      (node (ref "R11") (pin "2") (pinfunction "2_2") (pintype "passive"))
      (node (ref "U10") (pin "2") (pinfunction "2_2") (pintype "passive"))
    )
    (net (code "51") (name "Net-(Q5-D)") (class "Default")
      (node (ref "J2") (pin "1") (pinfunction "1_1") (pintype "passive"))
      (node (ref "Q5") (pin "3") (pinfunction "D_3") (pintype "passive"))
    )
    (net (code "52") (name "Net-(RN3-Pad1)") (class "Default")
      (node (ref "RN3") (pin "1") (pinfunction "1_1") (pintype "passive"))
      (node (ref "RN3") (pin "2") (pinfunction "2_2") (pintype "passive"))
    )
    (net (code "53") (name "Net-(RN3-Pad3)") (class "Default")
      (node (ref "RN3") (pin "3") (pinfunction "3_3") (pintype "passive"))
      (node (ref "RN3") (pin "4") (pinfunction "4_4") (pintype "passive"))
    )
    (net (code "54") (name "Net-(U1-EN)") (class "Default")
      (node (ref "C26") (pin "1") (pinfunction "1_1") (pintype "passive"))
      (node (ref "R9") (pin "2") (pinfunction "2_2") (pintype "passive"))
      (node (ref "SW4") (pin "2") (pinfunction "2_2") (pintype "passive"))
      (node (ref "U1") (pin "3") (pinfunction "EN_3") (pintype "passive"))
    )
    (net (code "55") (name "Net-(U1-IO0)") (class "Default")
      (node (ref "SW5") (pin "2") (pinfunction "2_2") (pintype "passive"))
      (node (ref "TP5") (pin "1") (pinfunction "1_1") (pintype "passive"))
      (node (ref "U1") (pin "25") (pinfunction "IO0_25") (pintype "passive"))
    )
    (net (code "56") (name "Net-(U3-V3)") (class "Default")
      (node (ref "C1") (pin "1") (pinfunction "1_1") (pintype "passive"))
      (node (ref "U3") (pin "8") (pinfunction "V3_8") (pintype "passive"))
    )
    (net (code "57") (name "Net-(U4-CHRG#)") (class "Default")
      (node (ref "R1") (pin "2") (pinfunction "2_2") (pintype "passive"))
      (node (ref "U4") (pin "7") (pinfunction "CHRG#_7") (pintype "passive"))
    )
    (net (code "58") (name "Net-(U4-PROG)") (class "Default")
      (node (ref "R3") (pin "2") (pinfunction "2_2") (pintype "passive"))
      (node (ref "U4") (pin "2") (pinfunction "PROG_2") (pintype "passive"))
    )
    (net (code "59") (name "Net-(U4-STDBY#)") (class "Default")
      (node (ref "R2") (pin "2") (pinfunction "2_2") (pintype "passive"))
      (node (ref "U4") (pin "6") (pinfunction "STDBY#_6") (pintype "passive"))
    )
    (net (code "60") (name "Net-(U5-EN)") (class "Default")
      (node (ref "C5") (pin "1") (pinfunction "1_1") (pintype "passive"))
      (node (ref "U5") (pin "1") (pinfunction "VINA_1") (pintype "passive"))
      (node (ref "U5") (pin "12") (pinfunction "EN_12") (pintype "passive"))
      (node (ref "U5") (pin "13") (pinfunction "PS/SYNC_13") (pintype "passive"))
    )
    (net (code "61") (name "Net-(U5-FB)") (class "Default")
      (node (ref "R5") (pin "1") (pinfunction "1_1") (pintype "passive"))
      (node (ref "R6") (pin "2") (pinfunction "2_2") (pintype "passive"))
      (node (ref "U5") (pin "3") (pinfunction "FB_3") (pintype "passive"))
    )
    (net (code "62") (name "Net-(U5-PG)") (class "Default")
      (node (ref "R4") (pin "2") (pinfunction "2_2") (pintype "passive"))
      (node (ref "U5") (pin "14") (pinfunction "PG_14") (pintype "passive"))
    )
    (net (code "63") (name "POWER") (class "Default")
      (node (ref "C6") (pin "2") (pinfunction "2_2") (pintype "passive"))
      (node (ref "C7") (pin "2") (pinfunction "2_2") (pintype "passive"))
      (node (ref "C8") (pin "2") (pinfunction "2_2") (pintype "passive"))
      (node (ref "D4") (pin "1") (pinfunction "C_1") (pintype "passive"))
      (node (ref "Q2") (pin "2") (pinfunction "S_2") (pintype "passive"))
      (node (ref "TP4") (pin "1") (pinfunction "1_1") (pintype "passive"))
      (node (ref "U5") (pin "10") (pinfunction "VIN_10") (pintype "passive"))
      (node (ref "U5") (pin "11") (pinfunction "VIN_11") (pintype "passive"))
    )
    (net (code "64") (name "VCC") (class "Default")
      (node (ref "C2") (pin "2") (pinfunction "2_2") (pintype "passive"))
      (node (ref "C3") (pin "1") (pinfunction "1_1") (pintype "passive"))
      (node (ref "D4") (pin "2") (pinfunction "A_2") (pintype "passive"))
      (node (ref "LED1") (pin "1") (pinfunction "1_1") (pintype "passive"))
      (node (ref "LED2") (pin "1") (pinfunction "1_1") (pintype "passive"))
      (node (ref "Q2") (pin "1") (pinfunction "G_1") (pintype "passive"))
      (node (ref "R10") (pin "2") (pinfunction "2_2") (pintype "passive"))
      (node (ref "TP1") (pin "1") (pinfunction "1_1") (pintype "passive"))
      (node (ref "U3") (pin "5") (pinfunction "VCC_5") (pintype "passive"))
      (node (ref "U4") (pin "4") (pinfunction "VCC_4") (pintype "passive"))
      (node (ref "U4") (pin "8") (pinfunction "CE_8") (pintype "passive"))
      (node (ref "USB1") (pin "A4") (pinfunction "VBUS_A4") (pintype "passive"))
      (node (ref "USB1") (pin "A9") (pinfunction "VBUS_A9") (pintype "passive"))
      (node (ref "USB1") (pin "B4") (pinfunction "VBUS_B4") (pintype "passive"))
      (node (ref "USB1") (pin "B9") (pinfunction "VBUS_B9") (pintype "passive"))
    )
    (net (code "65") (name "unconnected-(P1-HLT_CTL-Pad1)") (class "Default")
      (node (ref "P1") (pin "1") (pinfunction "HLT_CTL_1") (pintype "passive+no_connect"))
    )
    (net (code "66") (name "unconnected-(P1-Pad25)") (class "Default")
      (node (ref "P1") (pin "25") (pinfunction "25_25") (pintype "passive+no_connect"))
    )
    (net (code "67") (name "unconnected-(P1-Pad26)") (class "Default")
      (node (ref "P1") (pin "26") (pinfunction "26_26") (pintype "passive+no_connect"))
    )
    (net (code "68") (name "unconnected-(P1-TSCL-Pad6)") (class "Default")
      (node (ref "P1") (pin "6") (pinfunction "TSCL_6") (pintype "passive+no_connect"))
    )
    (net (code "69") (name "unconnected-(P1-TSDA-Pad7)") (class "Default")
      (node (ref "P1") (pin "7") (pinfunction "TSDA_7") (pintype "passive+no_connect"))
    )
    (net (code "70") (name "unconnected-(SW4-Pad3)") (class "Default")
      (node (ref "SW4") (pin "3") (pinfunction "3_3") (pintype "passive+no_connect"))
    )
    (net (code "71") (name "unconnected-(SW4-Pad4)") (class "Default")
      (node (ref "SW4") (pin "4") (pinfunction "4_4") (pintype "passive+no_connect"))
    )
    (net (code "72") (name "unconnected-(SW5-Pad3)") (class "Default")
      (node (ref "SW5") (pin "3") (pinfunction "3_3") (pintype "passive+no_connect"))
    )
    (net (code "73") (name "unconnected-(SW5-Pad4)") (class "Default")
      (node (ref "SW5") (pin "4") (pinfunction "4_4") (pintype "passive+no_connect"))
    )
    (net (code "74") (name "unconnected-(U1-NC-Pad17)") (class "Default")
      (node (ref "U1") (pin "17") (pinfunction "NC_17") (pintype "passive+no_connect"))
    )
    (net (code "75") (name "unconnected-(U1-NC-Pad18)") (class "Default")
      (node (ref "U1") (pin "18") (pinfunction "NC_18") (pintype "passive+no_connect"))
    )
    (net (code "76") (name "unconnected-(U1-NC-Pad19)") (class "Default")
      (node (ref "U1") (pin "19") (pinfunction "NC_19") (pintype "passive+no_connect"))
    )
    (net (code "77") (name "unconnected-(U1-NC-Pad20)") (class "Default")
      (node (ref "U1") (pin "20") (pinfunction "NC_20") (pintype "passive+no_connect"))
    )
    (net (code "78") (name "unconnected-(U1-NC-Pad21)") (class "Default")
      (node (ref "U1") (pin "21") (pinfunction "NC_21") (pintype "passive+no_connect"))
    )
    (net (code "79") (name "unconnected-(U1-NC-Pad22)") (class "Default")
      (node (ref "U1") (pin "22") (pinfunction "NC_22") (pintype "passive+no_connect"))
    )
    (net (code "80") (name "unconnected-(U1-NC-Pad32)") (class "Default")
      (node (ref "U1") (pin "32") (pinfunction "NC_32") (pintype "passive+no_connect"))
    )
    (net (code "81") (name "unconnected-(U3-RTS#-Pad4)") (class "Default")
      (node (ref "U3") (pin "4") (pinfunction "RTS#_4") (pintype "passive+no_connect"))
    )
    (net (code "82") (name "unconnected-(USB1-CC1-PadA5)") (class "Default")
      (node (ref "USB1") (pin "A5") (pinfunction "CC1_A5") (pintype "passive+no_connect"))
    )
    (net (code "83") (name "unconnected-(USB1-CC2-PadB5)") (class "Default")
      (node (ref "USB1") (pin "B5") (pinfunction "CC2_B5") (pintype "passive+no_connect"))
    )
    (net (code "84") (name "unconnected-(USB1-SBU1-PadA8)") (class "Default")
      (node (ref "USB1") (pin "A8") (pinfunction "SBU1_A8") (pintype "passive+no_connect"))
    )
    (net (code "85") (name "unconnected-(USB1-SBU2-PadB8)") (class "Default")
      (node (ref "USB1") (pin "B8") (pinfunction "SBU2_B8") (pintype "passive+no_connect"))
    )
  )
)
